# RTL_SDR_DSDAMP_0V1.net
KiCad netlist of a schematic drawn in EAGLE
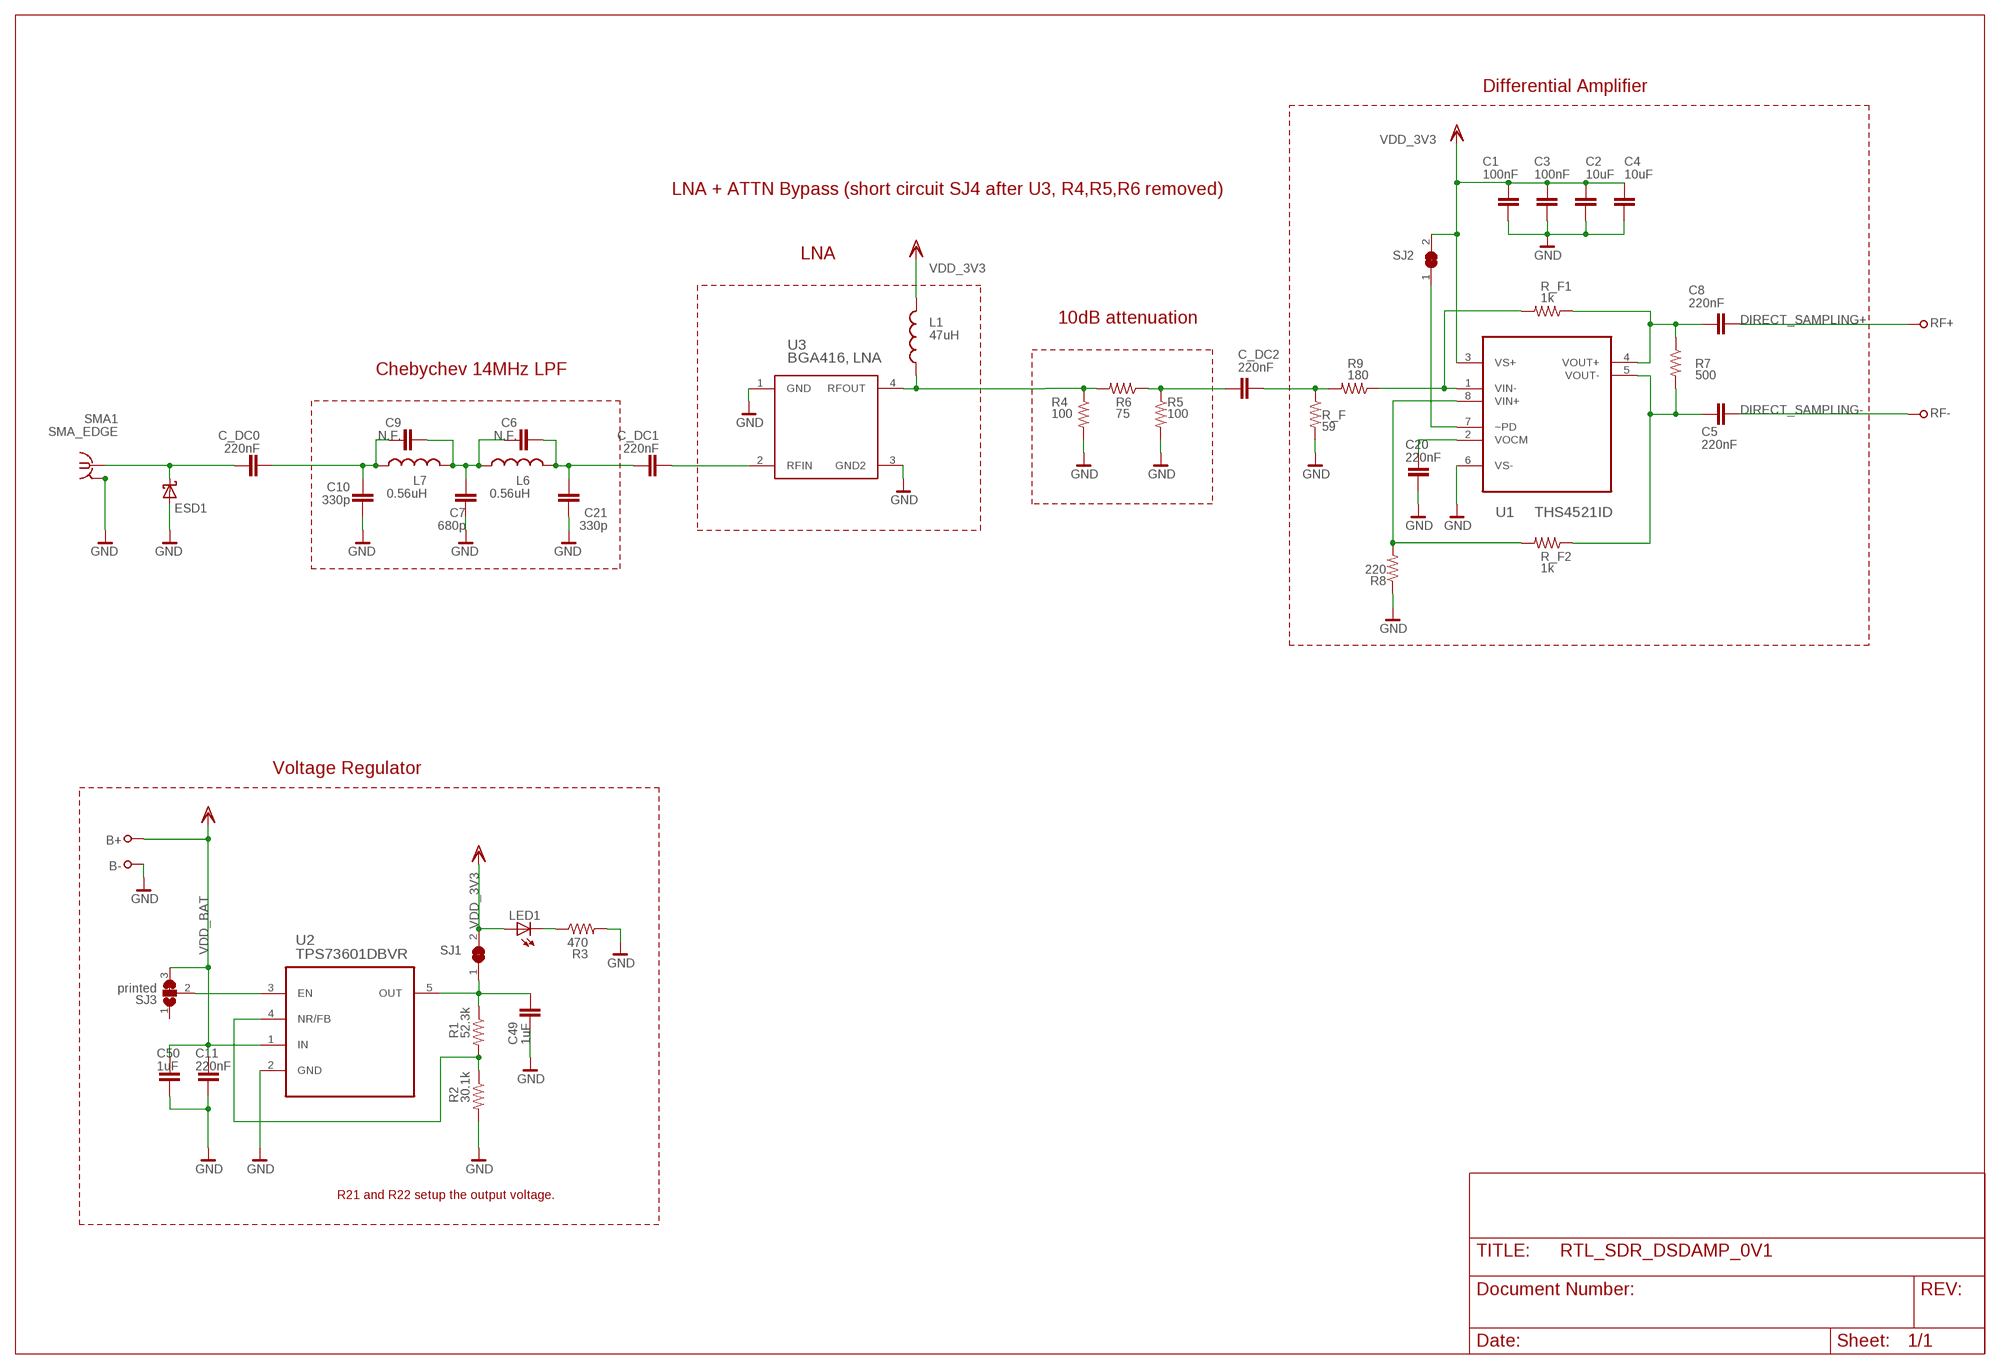
[diagram p0: schematic, sheet 1]

(export (version "E")
  (design (tool "Eeschema 10.0.6"))
  (components
    (comp (ref "B+")
      (value "TESTPOINT39MIL")
      (footprint "eagle-import:TESTPOINT1,0")
      (libsource (lib "eagle-import") (part "TESTPOINT39MIL"))
    )
    (comp (ref "B-")
      (value "TESTPOINT39MIL")
      (footprint "eagle-import:TESTPOINT1,0")
      (libsource (lib "eagle-import") (part "TESTPOINT39MIL"))
    )
    (comp (ref "C1")
      (value "100nF")
      (footprint "eagle-import:0603")
      (libsource (lib "eagle-import") (part "CAP-SMD0603"))
    )
    (comp (ref "C2")
      (value "100nF")
      (footprint "eagle-import:0603")
      (libsource (lib "eagle-import") (part "CAP-SMD0603"))
    )
    (comp (ref "C3")
      (value "10uF")
      (footprint "eagle-import:0603")
      (libsource (lib "eagle-import") (part "CAP-SMD0603"))
    )
    (comp (ref "C4")
      (value "10uF")
      (footprint "eagle-import:0603")
      (libsource (lib "eagle-import") (part "CAP-SMD0603"))
    )
    (comp (ref "C5")
      (value "220nF")
      (footprint "eagle-import:0603")
      (libsource (lib "eagle-import") (part "CAP-SMD0603"))
    )
    (comp (ref "C6")
      (value "N.F.")
      (footprint "eagle-import:0603")
      (libsource (lib "eagle-import") (part "CAP-SMD0603"))
    )
    (comp (ref "C7")
      (value "680p")
      (footprint "eagle-import:0603")
      (libsource (lib "eagle-import") (part "CAP-SMD0603"))
    )
    (comp (ref "C8")
      (value "220nF")
      (footprint "eagle-import:0603")
      (libsource (lib "eagle-import") (part "CAP-SMD0603"))
    )
    (comp (ref "C9")
      (value "N.F.")
      (footprint "eagle-import:0603")
      (libsource (lib "eagle-import") (part "CAP-SMD0603"))
    )
    (comp (ref "C10")
      (value "330p")
      (footprint "eagle-import:0603")
      (libsource (lib "eagle-import") (part "CAP-SMD0603"))
    )
    (comp (ref "C11")
      (value "220nF")
      (footprint "eagle-import:0603")
      (libsource (lib "eagle-import") (part "CAP-SMD0603"))
    )
    (comp (ref "C20")
      (value "220nF")
      (footprint "eagle-import:0603")
      (libsource (lib "eagle-import") (part "lve_modositott_CAP-SMD0603"))
    )
    (comp (ref "C21")
      (value "330p")
      (footprint "eagle-import:0603")
      (libsource (lib "eagle-import") (part "CAP-SMD0603"))
    )
    (comp (ref "C49")
      (value "1uF")
      (footprint "eagle-import:0603")
      (libsource (lib "eagle-import") (part "CAP-SMD0603"))
    )
    (comp (ref "C50")
      (value "1uF")
      (footprint "eagle-import:0603")
      (libsource (lib "eagle-import") (part "CAP-SMD0603"))
    )
    (comp (ref "C_DC0")
      (value "220nF")
      (footprint "eagle-import:0603")
      (libsource (lib "eagle-import") (part "CAP-SMD0603"))
    )
    (comp (ref "C_DC1")
      (value "220nF")
      (footprint "eagle-import:0603")
      (libsource (lib "eagle-import") (part "CAP-SMD0603"))
    )
    (comp (ref "C_DC2")
      (value "220nF")
      (footprint "eagle-import:0603")
      (libsource (lib "eagle-import") (part "CAP-SMD0603"))
    )
    (comp (ref "ESD1")
      (value "PGB1010603NRHF")
      (footprint "eagle-import:0603@1")
      (libsource (lib "eagle-import") (part "SMF33A-GS08_ESD0603"))
    )
    (comp (ref "L1")
      (value "47uH")
      (footprint "eagle-import:L1210")
      (libsource (lib "eagle-import") (part "INDUCTOR_L_1210"))
    )
    (comp (ref "L6")
      (value "0.56uH")
      (footprint "eagle-import:L1210")
      (libsource (lib "eagle-import") (part "INDUCTOR_L_1210"))
    )
    (comp (ref "L7")
      (value "0.56uH")
      (footprint "eagle-import:L1210")
      (libsource (lib "eagle-import") (part "INDUCTOR_L_1210"))
    )
    (comp (ref "LED1")
      (value "LED0603")
      (footprint "eagle-import:LED-0603")
      (libsource (lib "eagle-import") (part "LED0603"))
    )
    (comp (ref "R1")
      (value "52.3k")
      (footprint "eagle-import:R0603")
      (libsource (lib "eagle-import") (part "R-US_R0603"))
    )
    (comp (ref "R2")
      (value "30.1k")
      (footprint "eagle-import:R0603")
      (libsource (lib "eagle-import") (part "R-US_R0603"))
    )
    (comp (ref "R3")
      (value "470")
      (footprint "eagle-import:R0402")
      (libsource (lib "eagle-import") (part "R-US_R0402"))
    )
    (comp (ref "R4")
      (value "100")
      (footprint "eagle-import:R0603")
      (libsource (lib "eagle-import") (part "R-US_R0603"))
    )
    (comp (ref "R5")
      (value "100")
      (footprint "eagle-import:R0603")
      (libsource (lib "eagle-import") (part "R-US_R0603"))
    )
    (comp (ref "R6")
      (value "75")
      (footprint "eagle-import:R0603")
      (libsource (lib "eagle-import") (part "R-US_R0603"))
    )
    (comp (ref "R7")
      (value "500")
      (footprint "eagle-import:R0603")
      (libsource (lib "eagle-import") (part "R-US_R0603"))
    )
    (comp (ref "R8")
      (value "220")
      (footprint "eagle-import:R0603")
      (libsource (lib "eagle-import") (part "R-US_R0603"))
    )
    (comp (ref "R9")
      (value "180")
      (footprint "eagle-import:R0603")
      (libsource (lib "eagle-import") (part "R-US_R0603"))
    )
    (comp (ref "RF+")
      (value "TESTPOINT39MIL")
      (footprint "eagle-import:TESTPOINT1,0")
      (libsource (lib "eagle-import") (part "TESTPOINT39MIL"))
    )
    (comp (ref "RF-")
      (value "TESTPOINT39MIL")
      (footprint "eagle-import:TESTPOINT1,0")
      (libsource (lib "eagle-import") (part "TESTPOINT39MIL"))
    )
    (comp (ref "R_F")
      (value "59")
      (footprint "eagle-import:R0603")
      (libsource (lib "eagle-import") (part "R-US_R0603"))
    )
    (comp (ref "R_F1")
      (value "1k")
      (footprint "eagle-import:R0603")
      (libsource (lib "eagle-import") (part "R-US_R0603"))
    )
    (comp (ref "R_F2")
      (value "1k")
      (footprint "eagle-import:R0603")
      (libsource (lib "eagle-import") (part "R-US_R0603"))
    )
    (comp (ref "SJ1")
      (value "printed")
      (footprint "eagle-import:JUMPER_SMD_SJ_1")
      (libsource (lib "eagle-import") (part "JUMPER_SMD_1"))
    )
    (comp (ref "SJ2")
      (value "printed")
      (footprint "eagle-import:JUMPER_SMD_SJ_1")
      (libsource (lib "eagle-import") (part "JUMPER_SMD_1"))
    )
    (comp (ref "SJ3")
      (value "printed")
      (footprint "eagle-import:JUMPER_SMD_SJ2A")
      (libsource (lib "eagle-import") (part "JUMPER_SMD_3A"))
    )
    (comp (ref "SMA1")
      (value "SMA_EDGE")
      (footprint "eagle-import:142-0701-801")
      (libsource (lib "eagle-import") (part "SMA_EDGE"))
    )
    (comp (ref "U1")
      (value "THS4521ID")
      (footprint "eagle-import:SOIC127P600X175-8N")
      (libsource (lib "eagle-import") (part "THS4521ID"))
    )
    (comp (ref "U2")
      (value "TPS73601DBVR")
      (footprint "eagle-import:SOT95P280X145-5N")
      (libsource (lib "eagle-import") (part "TPS73601DBVR"))
    )
    (comp (ref "U3")
      (value "BGA416, LNA")
      (footprint "eagle-import:SOT143")
      (libsource (lib "eagle-import") (part "BGA416"))
    )
  )
  (nets
    (net (code "1") (name "/DIRECT_SAMPLING+") (class "Default")
      (node (ref "C8") (pin "1") (pinfunction "1_1") (pintype "passive"))
      (node (ref "RF+") (pin "1") (pinfunction "P$1_1") (pintype "passive"))
    )
    (net (code "2") (name "/DIRECT_SAMPLING-") (class "Default")
      (node (ref "C5") (pin "1") (pinfunction "1_1") (pintype "passive"))
      (node (ref "RF-") (pin "1") (pinfunction "P$1_1") (pintype "passive"))
    )
    (net (code "3") (name "GND") (class "Default")
      (node (ref "B-") (pin "1") (pinfunction "P$1_1") (pintype "passive"))
      (node (ref "C1") (pin "1") (pinfunction "1_1") (pintype "passive"))
      (node (ref "C10") (pin "1") (pinfunction "1_1") (pintype "passive"))
      (node (ref "C11") (pin "1") (pinfunction "1_1") (pintype "passive"))
      (node (ref "C2") (pin "1") (pinfunction "1_1") (pintype "passive"))
      (node (ref "C20") (pin "1") (pinfunction "1_1") (pintype "passive"))
      (node (ref "C21") (pin "1") (pinfunction "1_1") (pintype "passive"))
      (node (ref "C3") (pin "1") (pinfunction "1_1") (pintype "passive"))
      (node (ref "C4") (pin "1") (pinfunction "1_1") (pintype "passive"))
      (node (ref "C49") (pin "1") (pinfunction "1_1") (pintype "passive"))
      (node (ref "C50") (pin "1") (pinfunction "1_1") (pintype "passive"))
      (node (ref "C7") (pin "1") (pinfunction "1_1") (pintype "passive"))
      (node (ref "ESD1") (pin "1") (pinfunction "A_1") (pintype "passive"))
      (node (ref "R2") (pin "2") (pinfunction "2_2") (pintype "passive"))
      (node (ref "R3") (pin "2") (pinfunction "2_2") (pintype "passive"))
      (node (ref "R4") (pin "2") (pinfunction "2_2") (pintype "passive"))
      (node (ref "R5") (pin "2") (pinfunction "2_2") (pintype "passive"))
      (node (ref "R8") (pin "1") (pinfunction "1_1") (pintype "passive"))
      (node (ref "R_F") (pin "2") (pinfunction "2_2") (pintype "passive"))
      (node (ref "SMA1") (pin "RING@1") (pinfunction "2_RING@1") (pintype "passive"))
      (node (ref "SMA1") (pin "RING@2") (pinfunction "3_RING@2") (pintype "passive"))
      (node (ref "SMA1") (pin "RING@3") (pinfunction "4_RING@3") (pintype "passive"))
      (node (ref "SMA1") (pin "RING@4") (pinfunction "5_RING@4") (pintype "passive"))
      (node (ref "U1") (pin "6") (pinfunction "VS-_6") (pintype "power_in"))
      (node (ref "U2") (pin "2") (pinfunction "GND_2") (pintype "passive"))
      (node (ref "U3") (pin "1") (pinfunction "GND_1") (pintype "power_in"))
      (node (ref "U3") (pin "3") (pinfunction "GND2_3") (pintype "power_in"))
    )
    (net (code "4") (name "Net-(C6-Pad1)") (class "Default")
      (node (ref "C6") (pin "1") (pinfunction "1_1") (pintype "passive"))
      (node (ref "C7") (pin "2") (pinfunction "2_2") (pintype "passive"))
      (node (ref "C9") (pin "2") (pinfunction "2_2") (pintype "passive"))
      (node (ref "L6") (pin "2") (pinfunction "2_2") (pintype "passive"))
      (node (ref "L7") (pin "1") (pinfunction "1_1") (pintype "passive"))
    )
    (net (code "5") (name "Net-(C10-Pad2)") (class "Default")
      (node (ref "C10") (pin "2") (pinfunction "2_2") (pintype "passive"))
      (node (ref "C9") (pin "1") (pinfunction "1_1") (pintype "passive"))
      (node (ref "C_DC0") (pin "2") (pinfunction "2_2") (pintype "passive"))
      (node (ref "L7") (pin "2") (pinfunction "2_2") (pintype "passive"))
    )
    (net (code "6") (name "Net-(C21-Pad2)") (class "Default")
      (node (ref "C21") (pin "2") (pinfunction "2_2") (pintype "passive"))
      (node (ref "C6") (pin "2") (pinfunction "2_2") (pintype "passive"))
      (node (ref "C_DC1") (pin "1") (pinfunction "1_1") (pintype "passive"))
      (node (ref "L6") (pin "1") (pinfunction "1_1") (pintype "passive"))
    )
    (net (code "7") (name "Net-(C_DC2-Pad1)") (class "Default")
      (node (ref "C_DC2") (pin "1") (pinfunction "1_1") (pintype "passive"))
      (node (ref "R5") (pin "1") (pinfunction "1_1") (pintype "passive"))
      (node (ref "R6") (pin "1") (pinfunction "1_1") (pintype "passive"))
    )
    (net (code "8") (name "Net-(C_DC2-Pad2)") (class "Default")
      (node (ref "C_DC2") (pin "2") (pinfunction "2_2") (pintype "passive"))
      (node (ref "R9") (pin "2") (pinfunction "2_2") (pintype "passive"))
      (node (ref "R_F") (pin "1") (pinfunction "1_1") (pintype "passive"))
    )
    (net (code "9") (name "Net-(ESD1-C)") (class "Default")
      (node (ref "C_DC0") (pin "1") (pinfunction "1_1") (pintype "passive"))
      (node (ref "ESD1") (pin "2") (pinfunction "C_2") (pintype "passive"))
      (node (ref "SMA1") (pin "TIP") (pinfunction "1_TIP") (pintype "passive"))
    )
    (net (code "10") (name "Net-(LED1-PadC)") (class "Default")
      (node (ref "LED1") (pin "C") (pinfunction "C_C") (pintype "passive"))
      (node (ref "R3") (pin "1") (pinfunction "1_1") (pintype "passive"))
    )
    (net (code "11") (name "Net-(U1-VIN+)") (class "Default")
      (node (ref "R8") (pin "2") (pinfunction "2_2") (pintype "passive"))
      (node (ref "R_F2") (pin "2") (pinfunction "2_2") (pintype "passive"))
      (node (ref "U1") (pin "8") (pinfunction "VIN+_8") (pintype "input"))
    )
    (net (code "12") (name "Net-(U1-VIN-)") (class "Default")
      (node (ref "R9") (pin "1") (pinfunction "1_1") (pintype "passive"))
      (node (ref "R_F1") (pin "2") (pinfunction "2_2") (pintype "passive"))
      (node (ref "U1") (pin "1") (pinfunction "VIN-_1") (pintype "input"))
    )
    (net (code "13") (name "Net-(U1-VOCM)") (class "Default")
      (node (ref "C20") (pin "2") (pinfunction "2_2") (pintype "passive"))
      (node (ref "U1") (pin "2") (pinfunction "VOCM_2") (pintype "input"))
    )
    (net (code "14") (name "Net-(U1-VOUT+)") (class "Default")
      (node (ref "C8") (pin "2") (pinfunction "2_2") (pintype "passive"))
      (node (ref "R7") (pin "1") (pinfunction "1_1") (pintype "passive"))
      (node (ref "R_F1") (pin "1") (pinfunction "1_1") (pintype "passive"))
      (node (ref "U1") (pin "4") (pinfunction "VOUT+_4") (pintype "output"))
    )
    (net (code "15") (name "Net-(U1-VOUT-)") (class "Default")
      (node (ref "C5") (pin "2") (pinfunction "2_2") (pintype "passive"))
      (node (ref "R7") (pin "2") (pinfunction "2_2") (pintype "passive"))
      (node (ref "R_F2") (pin "1") (pinfunction "1_1") (pintype "passive"))
      (node (ref "U1") (pin "5") (pinfunction "VOUT-_5") (pintype "output"))
    )
    (net (code "16") (name "Net-(U1-~{PD})") (class "Default")
      (node (ref "SJ2") (pin "1") (pinfunction "1_1") (pintype "passive"))
      (node (ref "U1") (pin "7") (pinfunction "~{PD}_7") (pintype "input"))
    )
    (net (code "17") (name "Net-(U2-EN)") (class "Default")
      (node (ref "SJ3") (pin "2") (pinfunction "2_2") (pintype "passive"))
      (node (ref "U2") (pin "3") (pinfunction "EN_3") (pintype "input"))
    )
    (net (code "18") (name "Net-(U2-NR{slash}FB)") (class "Default")
      (node (ref "R1") (pin "2") (pinfunction "2_2") (pintype "passive"))
      (node (ref "R2") (pin "1") (pinfunction "1_1") (pintype "passive"))
      (node (ref "U2") (pin "4") (pinfunction "NR/FB_4") (pintype "input"))
    )
    (net (code "19") (name "Net-(U2-OUT)") (class "Default")
      (node (ref "C49") (pin "2") (pinfunction "2_2") (pintype "passive"))
      (node (ref "R1") (pin "1") (pinfunction "1_1") (pintype "passive"))
      (node (ref "SJ1") (pin "1") (pinfunction "1_1") (pintype "passive"))
      (node (ref "U2") (pin "5") (pinfunction "OUT_5") (pintype "power_in"))
    )
    (net (code "20") (name "Net-(U3-RFIN)") (class "Default")
      (node (ref "C_DC1") (pin "2") (pinfunction "2_2") (pintype "passive"))
      (node (ref "U3") (pin "2") (pinfunction "RFIN_2") (pintype "bidirectional"))
    )
    (net (code "21") (name "Net-(U3-RFOUT)") (class "Default")
      (node (ref "L1") (pin "2") (pinfunction "2_2") (pintype "passive"))
      (node (ref "R4") (pin "1") (pinfunction "1_1") (pintype "passive"))
      (node (ref "R6") (pin "2") (pinfunction "2_2") (pintype "passive"))
      (node (ref "U3") (pin "4") (pinfunction "RFOUT_4") (pintype "bidirectional"))
    )
    (net (code "22") (name "VDD_3V3") (class "Default")
      (node (ref "C1") (pin "2") (pinfunction "2_2") (pintype "passive"))
      (node (ref "C2") (pin "2") (pinfunction "2_2") (pintype "passive"))
      (node (ref "C3") (pin "2") (pinfunction "2_2") (pintype "passive"))
      (node (ref "C4") (pin "2") (pinfunction "2_2") (pintype "passive"))
      (node (ref "L1") (pin "1") (pinfunction "1_1") (pintype "passive"))
      (node (ref "LED1") (pin "A") (pinfunction "A_A") (pintype "passive"))
      (node (ref "SJ1") (pin "2") (pinfunction "2_2") (pintype "passive"))
      (node (ref "SJ2") (pin "2") (pinfunction "2_2") (pintype "passive"))
      (node (ref "U1") (pin "3") (pinfunction "VS+_3") (pintype "power_in"))
    )
    (net (code "23") (name "VDD_BAT") (class "Default")
      (node (ref "B+") (pin "1") (pinfunction "P$1_1") (pintype "passive"))
      (node (ref "C11") (pin "2") (pinfunction "2_2") (pintype "passive"))
      (node (ref "C50") (pin "2") (pinfunction "2_2") (pintype "passive"))
      (node (ref "SJ3") (pin "3") (pinfunction "3_3") (pintype "passive"))
      (node (ref "U2") (pin "1") (pinfunction "IN_1") (pintype "power_in"))
    )
    (net (code "24") (name "unconnected-(SJ3-Pad1)") (class "Default")
      (node (ref "SJ3") (pin "1") (pinfunction "1_1") (pintype "passive"))
    )
  )
)
